# CH32L103F8P-R0.net
KiCad netlist of a schematic drawn in Altium Designer
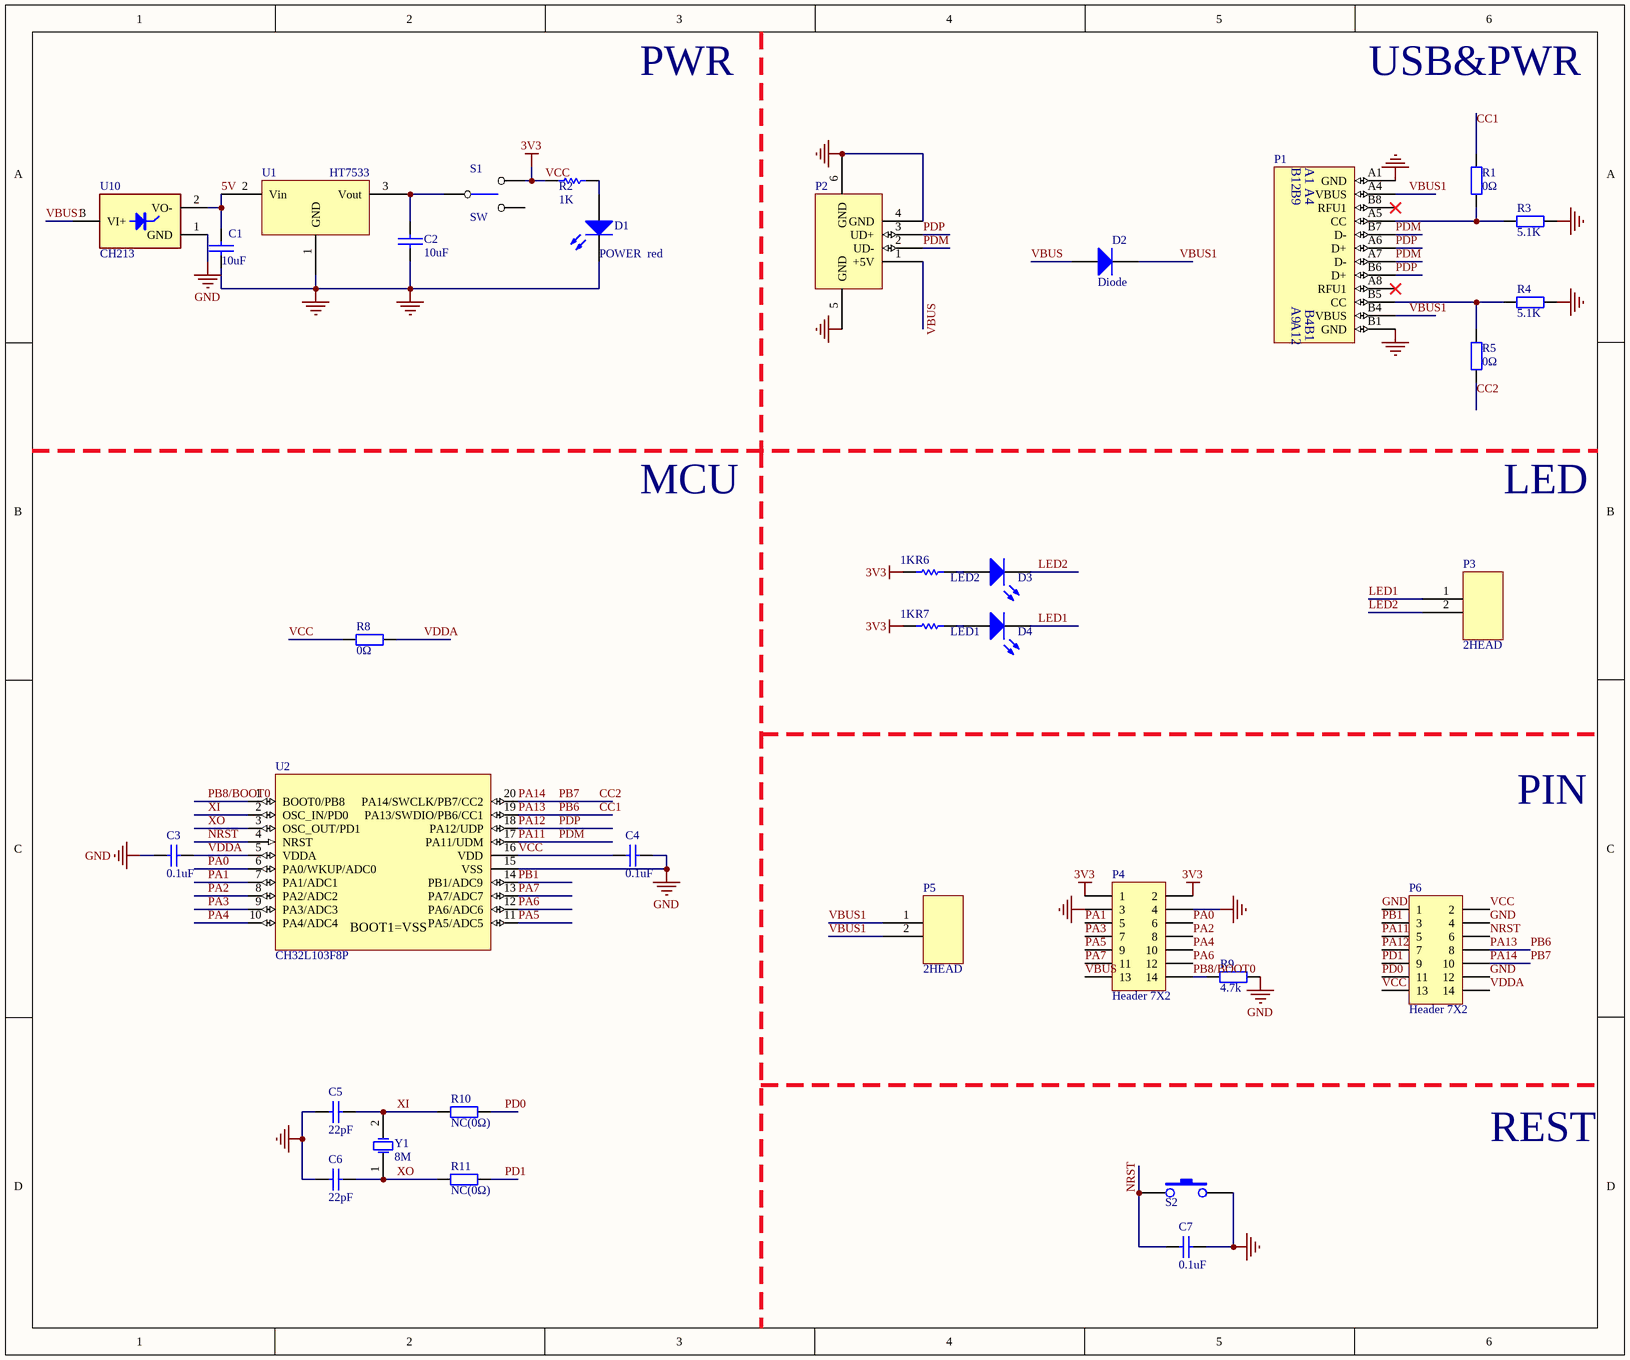
[diagram p0: CH32L103F8P-R0.SchDoc]

(export (version "E")
  (design (tool "Eeschema 10.0.6"))
  (components
    (comp (ref "C1")
      (value "10uF")
      (footprint "0603_C")
      (description "Capacitor")
      (libsource (lib "*") (part "CAP"))
    )
    (comp (ref "C2")
      (value "10uF")
      (footprint "0603_C")
      (description "Capacitor")
      (libsource (lib "*") (part "CAP"))
    )
    (comp (ref "C3")
      (value "0.1uF")
      (footprint "0603_C")
      (description "Capacitor")
      (fields (field (name "PUBLISHER") "Altium Limited"))
      (libsource (lib "*") (part "Cap"))
    )
    (comp (ref "C4")
      (value "0.1uF")
      (footprint "0603_C")
      (description "Capacitor")
      (fields (field (name "PUBLISHER") "Altium Limited"))
      (libsource (lib "*") (part "Cap"))
    )
    (comp (ref "C5")
      (value "22pF")
      (footprint "0603_C")
      (description "Capacitor")
      (fields (field (name "PUBLISHER") "Altium Limited"))
      (libsource (lib "*") (part "Cap"))
    )
    (comp (ref "C6")
      (value "22pF")
      (footprint "0603_C")
      (description "Capacitor")
      (fields (field (name "PUBLISHER") "Altium Limited"))
      (libsource (lib "*") (part "Cap"))
    )
    (comp (ref "C7")
      (value "0.1uF")
      (footprint "0603_C")
      (description "Capacitor")
      (fields (field (name "PUBLISHER") "Altium Limited"))
      (libsource (lib "*") (part "Cap"))
    )
    (comp (ref "D1")
      (value "POWER  red")
      (footprint "0603+")
      (description "Typical INFRARED GaAs LED")
      (fields (field (name "PUBLISHER") "Altium Limited"))
      (libsource (lib "*") (part "LED0"))
    )
    (comp (ref "D2")
      (value "Diode")
      (footprint "SOD-123")
      (description "Default Diode")
      (fields (field (name "PUBLISHER") "Altium Limited"))
      (libsource (lib "Miscellaneous Devices") (part "Diode"))
    )
    (comp (ref "D3")
      (value "LED2")
      (footprint "0603+")
      (description "Typical INFRARED GaAs LED")
      (fields (field (name "PUBLISHER") "Altium Limited"))
      (libsource (lib "*") (part "LED0"))
    )
    (comp (ref "D4")
      (value "LED1")
      (footprint "0603+")
      (description "Typical INFRARED GaAs LED")
      (fields (field (name "PUBLISHER") "Altium Limited"))
      (libsource (lib "*") (part "LED0"))
    )
    (comp (ref "P1")
      (value "TYPE-C")
      (footprint "TYPE-C-Receptacle-2.0")
      (libsource (lib "*") (part "TYPE-C1"))
    )
    (comp (ref "P2")
      (value "USB_A")
      (footprint "USBAF")
      (description "USB Port")
      (libsource (lib "*") (part "USB"))
    )
    (comp (ref "P3") (value "2HEAD") (footprint "SIP2-2.54mm") (libsource (lib "*") (part "2HEAD")))
    (comp (ref "P4")
      (value "Header 7X2")
      (footprint "IDC14-2.54mm")
      (description "Header, 7-Pin, Dual row")
      (fields (field (name "PUBLISHER") "Altium Limited"))
      (libsource (lib "Miscellaneous Connectors") (part "Header 7X2"))
    )
    (comp (ref "P5") (value "2HEAD") (footprint "SIP2-2.54mm") (libsource (lib "*") (part "2HEAD")))
    (comp (ref "P6")
      (value "Header 7X2")
      (footprint "IDC14-2.54mm")
      (description "Header, 7-Pin, Dual row")
      (fields (field (name "PUBLISHER") "Altium Limited"))
      (libsource (lib "Miscellaneous Connectors") (part "Header 7X2"))
    )
    (comp (ref "R1")
      (value "0Ω")
      (footprint "0603")
      (description "Resistor")
      (libsource (lib "") (part "Res2_1"))
    )
    (comp (ref "R2")
      (value "1K")
      (footprint "0603")
      (description "Semiconductor Resistor")
      (libsource (lib "*") (part "Res Semi"))
    )
    (comp (ref "R3")
      (value "5.1K")
      (footprint "0603")
      (description "Resistor")
      (libsource (lib "") (part "Res2_2"))
    )
    (comp (ref "R4")
      (value "5.1K")
      (footprint "0603")
      (description "Resistor")
      (libsource (lib "") (part "Res2_2"))
    )
    (comp (ref "R5")
      (value "0Ω")
      (footprint "0603")
      (description "Resistor")
      (libsource (lib "") (part "Res2_1"))
    )
    (comp (ref "R6")
      (value "1K")
      (footprint "0603")
      (description "Semiconductor Resistor")
      (libsource (lib "*") (part "Res Semi"))
    )
    (comp (ref "R7")
      (value "1K")
      (footprint "0603")
      (description "Semiconductor Resistor")
      (libsource (lib "*") (part "Res Semi"))
    )
    (comp (ref "R8")
      (value "0Ω")
      (footprint "0603")
      (description "Resistor")
      (libsource (lib "") (part "Res2_2"))
    )
    (comp (ref "R9")
      (value "4.7k")
      (footprint "0603")
      (description "Resistor")
      (libsource (lib "") (part "Res2_2"))
    )
    (comp (ref "R10")
      (value "NC(0Ω)")
      (footprint "0603")
      (description "Resistor")
      (libsource (lib "Miscellaneous Devices") (part "Res2"))
    )
    (comp (ref "R11")
      (value "NC(0Ω)")
      (footprint "0603")
      (description "Resistor")
      (libsource (lib "Miscellaneous Devices") (part "Res2"))
    )
    (comp (ref "S1") (value "SW") (footprint "SW1") (libsource (lib "*") (part "SW")))
    (comp (ref "S2") (value "KEY") (footprint "贴片按键") (libsource (lib "*") (part "KEY")))
    (comp (ref "U1")
      (value "HT7533")
      (footprint "SOT-89")
      (libsource (lib "wch_sch_others") (part "1117-3.3V"))
    )
    (comp (ref "U2")
      (value "CH32L103F8P")
      (footprint "TSSOP20")
      (description "RISC-V LMD-MCU, 96MHz, USB, Type-C/PD, CAN, OPA, lower power")
      (libsource (lib "CHXXX") (part "CH32L103F8P"))
    )
    (comp (ref "U10")
      (value "CH213")
      (footprint "SOT-23-3")
      (description "Ideal Diode 5V*1A")
      (libsource (lib "CHXXX") (part "CH213E"))
    )
    (comp (ref "Y1")
      (value "8M")
      (footprint "XT_AT49")
      (description "Crystal Oscillator")
      (fields (field (name "PUBLISHER") "Altium Limited"))
      (libsource (lib "*") (part "XTAL"))
    )
  )
  (nets
    (net (code "1") (name "/5V") (class "Default")
      (node (ref "C1") (pin "1") (pinfunction "1_1") (pintype "passive"))
      (node (ref "U1") (pin "2") (pinfunction "Vin_2") (pintype "passive"))
      (node (ref "U10") (pin "2") (pinfunction "VO-_2") (pintype "power_in"))
    )
    (net (code "3") (name "/CC1") (class "Default")
      (node (ref "P6") (pin "8") (pinfunction "8_8") (pintype "passive"))
      (node (ref "R1") (pin "2") (pinfunction "2_2") (pintype "passive"))
      (node (ref "U2") (pin "19") (pinfunction "PA13/SWDIO/PB6/CC1_19") (pintype "bidirectional"))
    )
    (net (code "4") (name "/CC2") (class "Default")
      (node (ref "P6") (pin "10") (pinfunction "10_10") (pintype "passive"))
      (node (ref "R5") (pin "1") (pinfunction "1_1") (pintype "passive"))
      (node (ref "U2") (pin "20") (pinfunction "PA14/SWCLK/PB7/CC2_20") (pintype "bidirectional"))
    )
    (net (code "5") (name "/LED1") (class "Default")
      (node (ref "D4") (pin "2") (pinfunction "K_2") (pintype "passive"))
      (node (ref "P3") (pin "1") (pintype "passive"))
    )
    (net (code "6") (name "/LED2") (class "Default")
      (node (ref "D3") (pin "2") (pinfunction "K_2") (pintype "passive"))
      (node (ref "P3") (pin "2") (pintype "passive"))
    )
    (net (code "7") (name "/NRST") (class "Default")
      (node (ref "C7") (pin "2") (pinfunction "2_2") (pintype "passive"))
      (node (ref "P6") (pin "6") (pinfunction "6_6") (pintype "passive"))
      (node (ref "S2") (pin "1") (pinfunction "1_1") (pintype "passive"))
      (node (ref "U2") (pin "4") (pinfunction "NRST_4") (pintype "input"))
    )
    (net (code "8") (name "/PA0") (class "Default")
      (node (ref "P4") (pin "6") (pinfunction "6_6") (pintype "passive"))
      (node (ref "U2") (pin "6") (pinfunction "PA0/WKUP/ADC0_6") (pintype "bidirectional"))
    )
    (net (code "9") (name "/PA1") (class "Default")
      (node (ref "P4") (pin "5") (pinfunction "5_5") (pintype "passive"))
      (node (ref "U2") (pin "7") (pinfunction "PA1/ADC1_7") (pintype "bidirectional"))
    )
    (net (code "10") (name "/PA2") (class "Default")
      (node (ref "P4") (pin "8") (pinfunction "8_8") (pintype "passive"))
      (node (ref "U2") (pin "8") (pinfunction "PA2/ADC2_8") (pintype "bidirectional"))
    )
    (net (code "11") (name "/PA3") (class "Default")
      (node (ref "P4") (pin "7") (pinfunction "7_7") (pintype "passive"))
      (node (ref "U2") (pin "9") (pinfunction "PA3/ADC3_9") (pintype "bidirectional"))
    )
    (net (code "12") (name "/PA4") (class "Default")
      (node (ref "P4") (pin "10") (pinfunction "10_10") (pintype "passive"))
      (node (ref "U2") (pin "10") (pinfunction "PA4/ADC4_10") (pintype "bidirectional"))
    )
    (net (code "13") (name "/PA5") (class "Default")
      (node (ref "P4") (pin "9") (pinfunction "9_9") (pintype "passive"))
      (node (ref "U2") (pin "11") (pinfunction "PA5/ADC5_11") (pintype "bidirectional"))
    )
    (net (code "14") (name "/PA6") (class "Default")
      (node (ref "P4") (pin "12") (pinfunction "12_12") (pintype "passive"))
      (node (ref "U2") (pin "12") (pinfunction "PA6/ADC6_12") (pintype "bidirectional"))
    )
    (net (code "15") (name "/PA7") (class "Default")
      (node (ref "P4") (pin "11") (pinfunction "11_11") (pintype "passive"))
      (node (ref "U2") (pin "13") (pinfunction "PA7/ADC7_13") (pintype "bidirectional"))
    )
    (net (code "16") (name "/PA11") (class "Default")
      (node (ref "P1") (pin "A7") (pinfunction "D-_A7") (pintype "bidirectional"))
      (node (ref "P1") (pin "B7") (pinfunction "D-_B7") (pintype "bidirectional"))
      (node (ref "P2") (pin "2") (pinfunction "UD-_2") (pintype "bidirectional"))
      (node (ref "P6") (pin "5") (pinfunction "5_5") (pintype "passive"))
      (node (ref "U2") (pin "17") (pinfunction "PA11/UDM_17") (pintype "bidirectional"))
    )
    (net (code "17") (name "/PA12") (class "Default")
      (node (ref "P1") (pin "A6") (pinfunction "D+_A6") (pintype "bidirectional"))
      (node (ref "P1") (pin "B6") (pinfunction "D+_B6") (pintype "bidirectional"))
      (node (ref "P2") (pin "3") (pinfunction "UD+_3") (pintype "bidirectional"))
      (node (ref "P6") (pin "7") (pinfunction "7_7") (pintype "passive"))
      (node (ref "U2") (pin "18") (pinfunction "PA12/UDP_18") (pintype "bidirectional"))
    )
    (net (code "18") (name "/PB1") (class "Default")
      (node (ref "P6") (pin "3") (pinfunction "3_3") (pintype "passive"))
      (node (ref "U2") (pin "14") (pinfunction "PB1/ADC9_14") (pintype "bidirectional"))
    )
    (net (code "19") (name "/PB8{slash}BOOT0") (class "Default")
      (node (ref "P4") (pin "14") (pinfunction "14_14") (pintype "passive"))
      (node (ref "R9") (pin "1") (pinfunction "1_1") (pintype "passive"))
      (node (ref "U2") (pin "1") (pinfunction "BOOT0/PB8_1") (pintype "bidirectional"))
    )
    (net (code "20") (name "/PD0") (class "Default")
      (node (ref "P6") (pin "11") (pinfunction "11_11") (pintype "passive"))
      (node (ref "R10") (pin "1") (pinfunction "1_1") (pintype "passive"))
    )
    (net (code "21") (name "/PD1") (class "Default")
      (node (ref "P6") (pin "9") (pinfunction "9_9") (pintype "passive"))
      (node (ref "R11") (pin "1") (pinfunction "1_1") (pintype "passive"))
    )
    (net (code "22") (name "/VBUS") (class "Default")
      (node (ref "D2") (pin "1") (pinfunction "A_1") (pintype "passive"))
      (node (ref "P2") (pin "1") (pinfunction "+5V_1") (pintype "power_in"))
      (node (ref "P4") (pin "13") (pinfunction "13_13") (pintype "passive"))
    )
    (net (code "23") (name "/VBUS1") (class "Default")
      (node (ref "D2") (pin "2") (pinfunction "K_2") (pintype "passive"))
      (node (ref "P1") (pin "A4") (pinfunction "VBUS_A4") (pintype "bidirectional"))
      (node (ref "P1") (pin "B4") (pinfunction "VBUS_B4") (pintype "bidirectional"))
      (node (ref "P5") (pin "1") (pintype "passive"))
      (node (ref "P5") (pin "2") (pintype "passive"))
      (node (ref "U10") (pin "3") (pinfunction "VI+_3") (pintype "power_in"))
    )
    (net (code "24") (name "/VDDA") (class "Default")
      (node (ref "C3") (pin "1") (pinfunction "1_1") (pintype "passive"))
      (node (ref "P6") (pin "14") (pinfunction "14_14") (pintype "passive"))
      (node (ref "R8") (pin "2") (pinfunction "2_2") (pintype "passive"))
      (node (ref "U2") (pin "5") (pinfunction "VDDA_5") (pintype "bidirectional"))
    )
    (net (code "25") (name "/XI") (class "Default")
      (node (ref "C5") (pin "2") (pinfunction "2_2") (pintype "passive"))
      (node (ref "R10") (pin "2") (pinfunction "2_2") (pintype "passive"))
      (node (ref "U2") (pin "2") (pinfunction "OSC_IN/PD0_2") (pintype "bidirectional"))
      (node (ref "Y1") (pin "2") (pinfunction "OSC2_2") (pintype "passive"))
    )
    (net (code "26") (name "/XO") (class "Default")
      (node (ref "C6") (pin "2") (pinfunction "2_2") (pintype "passive"))
      (node (ref "R11") (pin "2") (pinfunction "2_2") (pintype "passive"))
      (node (ref "U2") (pin "3") (pinfunction "OSC_OUT/PD1_3") (pintype "bidirectional"))
      (node (ref "Y1") (pin "1") (pinfunction "OSC1_1") (pintype "passive"))
    )
    (net (code "27") (name "3V3") (class "Default")
      (node (ref "C4") (pin "1") (pinfunction "1_1") (pintype "passive"))
      (node (ref "P4") (pin "1") (pinfunction "1_1") (pintype "passive"))
      (node (ref "P4") (pin "2") (pinfunction "2_2") (pintype "passive"))
      (node (ref "P6") (pin "13") (pinfunction "13_13") (pintype "passive"))
      (node (ref "P6") (pin "2") (pinfunction "2_2") (pintype "passive"))
      (node (ref "R2") (pin "2") (pinfunction "2_2") (pintype "passive"))
      (node (ref "R6") (pin "1") (pinfunction "1_1") (pintype "passive"))
      (node (ref "R7") (pin "1") (pinfunction "1_1") (pintype "passive"))
      (node (ref "R8") (pin "1") (pinfunction "1_1") (pintype "passive"))
      (node (ref "S1") (pin "3") (pinfunction "3_3") (pintype "passive"))
      (node (ref "U2") (pin "16") (pinfunction "VDD_16") (pintype "power_in"))
    )
    (net (code "28") (name "GND") (class "Default")
      (node (ref "C1") (pin "2") (pinfunction "2_2") (pintype "passive"))
      (node (ref "C2") (pin "2") (pinfunction "2_2") (pintype "passive"))
      (node (ref "C3") (pin "2") (pinfunction "2_2") (pintype "passive"))
      (node (ref "C4") (pin "2") (pinfunction "2_2") (pintype "passive"))
      (node (ref "C5") (pin "1") (pinfunction "1_1") (pintype "passive"))
      (node (ref "C6") (pin "1") (pinfunction "1_1") (pintype "passive"))
      (node (ref "C7") (pin "1") (pinfunction "1_1") (pintype "passive"))
      (node (ref "D1") (pin "2") (pinfunction "K_2") (pintype "passive"))
      (node (ref "P1") (pin "A1") (pinfunction "GND_A1") (pintype "bidirectional"))
      (node (ref "P1") (pin "B1") (pinfunction "GND_B1") (pintype "bidirectional"))
      (node (ref "P2") (pin "4") (pinfunction "GND_4") (pintype "power_in"))
      (node (ref "P2") (pin "5") (pinfunction "GND_5") (pintype "power_in"))
      (node (ref "P2") (pin "6") (pinfunction "GND_6") (pintype "power_in"))
      (node (ref "P4") (pin "3") (pinfunction "3_3") (pintype "passive"))
      (node (ref "P4") (pin "4") (pinfunction "4_4") (pintype "passive"))
      (node (ref "P6") (pin "1") (pinfunction "1_1") (pintype "passive"))
      (node (ref "P6") (pin "12") (pinfunction "12_12") (pintype "passive"))
      (node (ref "P6") (pin "4") (pinfunction "4_4") (pintype "passive"))
      (node (ref "R3") (pin "2") (pinfunction "2_2") (pintype "passive"))
      (node (ref "R4") (pin "2") (pinfunction "2_2") (pintype "passive"))
      (node (ref "R9") (pin "2") (pinfunction "2_2") (pintype "passive"))
      (node (ref "S2") (pin "3") (pinfunction "3_3") (pintype "passive"))
      (node (ref "U1") (pin "1") (pinfunction "GND_1") (pintype "passive"))
      (node (ref "U10") (pin "1") (pinfunction "GND_1") (pintype "power_in"))
      (node (ref "U2") (pin "15") (pinfunction "VSS_15") (pintype "power_in"))
    )
    (net (code "29") (name "Net-(D1-A)") (class "Default")
      (node (ref "D1") (pin "1") (pinfunction "A_1") (pintype "passive"))
      (node (ref "R2") (pin "1") (pinfunction "1_1") (pintype "passive"))
    )
    (net (code "30") (name "Net-(D3-A)") (class "Default")
      (node (ref "D3") (pin "1") (pinfunction "A_1") (pintype "passive"))
      (node (ref "R6") (pin "2") (pinfunction "2_2") (pintype "passive"))
    )
    (net (code "31") (name "Net-(D4-A)") (class "Default")
      (node (ref "D4") (pin "1") (pinfunction "A_1") (pintype "passive"))
      (node (ref "R7") (pin "2") (pinfunction "2_2") (pintype "passive"))
    )
    (net (code "32") (name "Net-(P1-CC-PadA5)") (class "Default")
      (node (ref "P1") (pin "A5") (pinfunction "CC_A5") (pintype "bidirectional"))
      (node (ref "R1") (pin "1") (pinfunction "1_1") (pintype "passive"))
      (node (ref "R3") (pin "1") (pinfunction "1_1") (pintype "passive"))
    )
    (net (code "33") (name "Net-(P1-CC-PadB5)") (class "Default")
      (node (ref "P1") (pin "B5") (pinfunction "CC_B5") (pintype "bidirectional"))
      (node (ref "R4") (pin "1") (pinfunction "1_1") (pintype "passive"))
      (node (ref "R5") (pin "2") (pinfunction "2_2") (pintype "passive"))
    )
    (net (code "34") (name "Net-(U1-Vout)") (class "Default")
      (node (ref "C2") (pin "1") (pinfunction "1_1") (pintype "passive"))
      (node (ref "S1") (pin "1") (pinfunction "1_1") (pintype "passive"))
      (node (ref "U1") (pin "3") (pinfunction "Vout_3") (pintype "passive"))
    )
    (net (code "35") (name "unconnected-(P1-RFU1-PadA8)") (class "Default")
      (node (ref "P1") (pin "A8") (pinfunction "RFU1_A8") (pintype "bidirectional+no_connect"))
    )
    (net (code "36") (name "unconnected-(P1-RFU1-PadB8)") (class "Default")
      (node (ref "P1") (pin "B8") (pinfunction "RFU1_B8") (pintype "bidirectional+no_connect"))
    )
    (net (code "37") (name "unconnected-(S1-Pad2)") (class "Default")
      (node (ref "S1") (pin "2") (pinfunction "2_2") (pintype "passive"))
    )
  )
)
